# QCopterMV_SD_Sch.net
KiCad netlist of a schematic drawn in Altium Designer
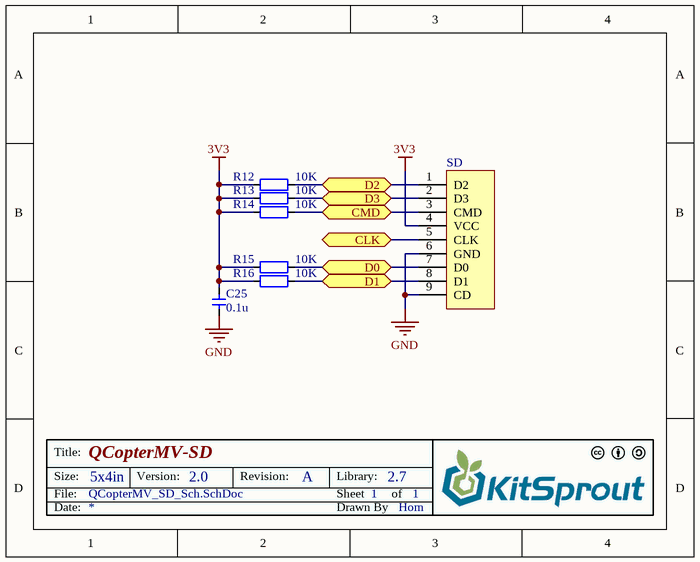
[diagram p0: QCopterMV_SD_Sch.SchDoc]

(export (version "E")
  (design (tool "Eeschema 10.0.6"))
  (components
    (comp (ref "C25")
      (value "0.1u")
      (footprint "PCB_PassiveCap:CAP_0402")
      (description "Capacitor")
      (fields (field (name "Comment") "Cap_0402"))
      (libsource (lib "SCH_Passive") (part "Cap_0402"))
    )
    (comp (ref "R12")
      (value "10K")
      (footprint "PCB_PassiveRes:RES_0402")
      (description "Resistor")
      (fields (field (name "Comment") "Res_0402"))
      (libsource (lib "SCH_Passive") (part "Res_0402"))
    )
    (comp (ref "R13")
      (value "10K")
      (footprint "PCB_PassiveRes:RES_0402")
      (description "Resistor")
      (fields (field (name "Comment") "Res_0402"))
      (libsource (lib "SCH_Passive") (part "Res_0402"))
    )
    (comp (ref "R14")
      (value "10K")
      (footprint "PCB_PassiveRes:RES_0402")
      (description "Resistor")
      (fields (field (name "Comment") "Res_0402"))
      (libsource (lib "SCH_Passive") (part "Res_0402"))
    )
    (comp (ref "R15")
      (value "10K")
      (footprint "PCB_PassiveRes:RES_0402")
      (description "Resistor")
      (fields (field (name "Comment") "Res_0402"))
      (libsource (lib "SCH_Passive") (part "Res_0402"))
    )
    (comp (ref "R16")
      (value "10K")
      (footprint "PCB_PassiveRes:RES_0402")
      (description "Resistor")
      (fields (field (name "Comment") "Res_0402"))
      (libsource (lib "SCH_Passive") (part "Res_0402"))
    )
    (comp (ref "SD")
      (value "SD_Card_TF")
      (footprint "PCB_SDCard:SD_Card_TF")
      (description "SD")
      (libsource (lib "SCH_SDCard") (part "SD_Card_TF"))
    )
  )
  (nets
    (net (code "1") (name "/CLK") (class "Default")
      (node (ref "SD") (pin "5") (pinfunction "CLK_5") (pintype "passive"))
    )
    (net (code "2") (name "/CMD") (class "Default")
      (node (ref "R14") (pin "2") (pinfunction "2_2") (pintype "passive"))
      (node (ref "SD") (pin "3") (pinfunction "CMD_3") (pintype "passive"))
    )
    (net (code "3") (name "/D0") (class "Default")
      (node (ref "R15") (pin "2") (pinfunction "2_2") (pintype "passive"))
      (node (ref "SD") (pin "7") (pinfunction "D0_7") (pintype "passive"))
    )
    (net (code "4") (name "/D1") (class "Default")
      (node (ref "R16") (pin "2") (pinfunction "2_2") (pintype "passive"))
      (node (ref "SD") (pin "8") (pinfunction "D1_8") (pintype "passive"))
    )
    (net (code "5") (name "/D2") (class "Default")
      (node (ref "R12") (pin "2") (pinfunction "2_2") (pintype "passive"))
      (node (ref "SD") (pin "1") (pinfunction "D2_1") (pintype "passive"))
    )
    (net (code "6") (name "/D3") (class "Default")
      (node (ref "R13") (pin "2") (pinfunction "2_2") (pintype "passive"))
      (node (ref "SD") (pin "2") (pinfunction "D3_2") (pintype "passive"))
    )
    (net (code "7") (name "3V3") (class "Default")
      (node (ref "C25") (pin "2") (pinfunction "2_2") (pintype "passive"))
      (node (ref "R12") (pin "1") (pinfunction "1_1") (pintype "passive"))
      (node (ref "R13") (pin "1") (pinfunction "1_1") (pintype "passive"))
      (node (ref "R14") (pin "1") (pinfunction "1_1") (pintype "passive"))
      (node (ref "R15") (pin "1") (pinfunction "1_1") (pintype "passive"))
      (node (ref "R16") (pin "1") (pinfunction "1_1") (pintype "passive"))
      (node (ref "SD") (pin "4") (pinfunction "VCC_4") (pintype "passive"))
    )
    (net (code "8") (name "GND") (class "Default")
      (node (ref "C25") (pin "1") (pinfunction "1_1") (pintype "passive"))
      (node (ref "SD") (pin "6") (pinfunction "GND_6") (pintype "passive"))
      (node (ref "SD") (pin "9") (pinfunction "CD_9") (pintype "passive"))
    )
  )
)
